# Pi3ToRFIDSchematic.net
KiCad netlist of a schematic drawn in EAGLE
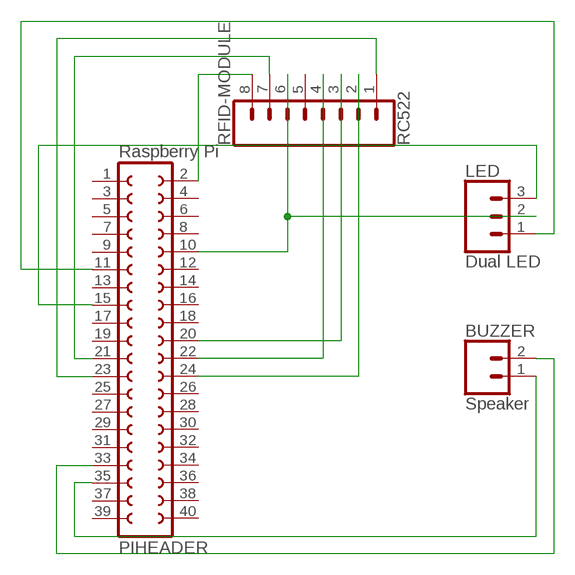
[diagram p0: schematic, sheet 1]
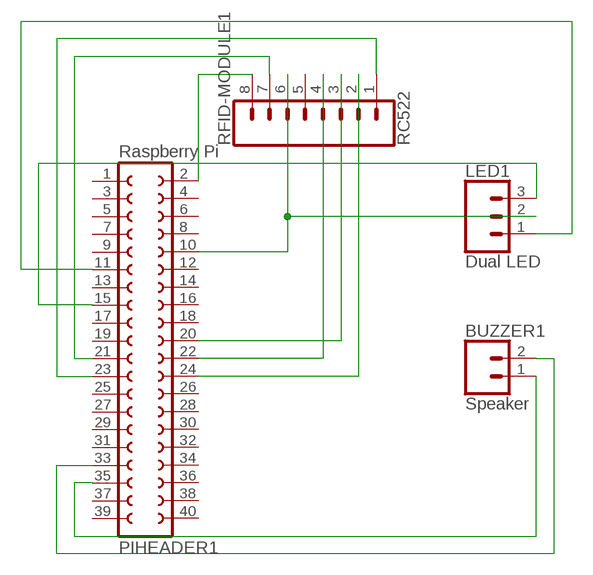
[diagram p1: schematic, sheet 2]

(export (version "E")
  (design (tool "Eeschema 10.0.6"))
  (components
    (comp (ref "BUZZER1")
      (value "Speaker")
      (footprint "eagle-import:MOLEX-1X2")
      (libsource (lib "eagle-import") (part "CONN_02POLAR"))
    )
    (comp (ref "LED1")
      (value "Dual LED")
      (footprint "eagle-import:MOLEX-1X3")
      (libsource (lib "eagle-import") (part "CONN_03POLAR"))
    )
    (comp (ref "PIHEADER1")
      (value "Raspberry Pi")
      (footprint "eagle-import:FE20-2W")
      (libsource (lib "eagle-import") (part "FE20-2W"))
    )
    (comp (ref "RFID-MODULE1")
      (value "RC522")
      (footprint "eagle-import:1X08_LONGPADS")
      (libsource (lib "eagle-import") (part "CONN_08LONGPADS"))
    )
    (comp (ref "BUZZER")
      (value "Speaker")
      (footprint "eagle-import:MOLEX-1X2")
      (libsource (lib "eagle-import") (part "CONN_02POLAR"))
    )
    (comp (ref "LED")
      (value "Dual LED")
      (footprint "eagle-import:MOLEX-1X3")
      (libsource (lib "eagle-import") (part "CONN_03POLAR"))
    )
    (comp (ref "PIHEADER")
      (value "Raspberry Pi")
      (footprint "eagle-import:FE20-2W")
      (libsource (lib "eagle-import") (part "FE20-2W"))
    )
    (comp (ref "RFID-MODULE")
      (value "RC522")
      (footprint "eagle-import:1X08_LONGPADS")
      (libsource (lib "eagle-import") (part "CONN_08LONGPADS"))
    )
  )
  (nets
    (net (code "1") (name "Net-(BUZZER-Pad1)") (class "Default")
      (node (ref "BUZZER") (pin "1") (pinfunction "1_1") (pintype "passive"))
      (node (ref "PIHEADER") (pin "35") (pinfunction "35_35") (pintype "passive"))
    )
    (net (code "2") (name "Net-(BUZZER-Pad2)") (class "Default")
      (node (ref "BUZZER") (pin "2") (pinfunction "2_2") (pintype "passive"))
      (node (ref "PIHEADER") (pin "33") (pinfunction "33_33") (pintype "passive"))
    )
    (net (code "3") (name "Net-(BUZZER1-Pad1)") (class "Default")
      (node (ref "BUZZER1") (pin "1") (pinfunction "1_1") (pintype "passive"))
      (node (ref "PIHEADER1") (pin "35") (pinfunction "35_35") (pintype "passive"))
    )
    (net (code "4") (name "Net-(BUZZER1-Pad2)") (class "Default")
      (node (ref "BUZZER1") (pin "2") (pinfunction "2_2") (pintype "passive"))
      (node (ref "PIHEADER1") (pin "33") (pinfunction "33_33") (pintype "passive"))
    )
    (net (code "5") (name "Net-(LED-Pad1)") (class "Default")
      (node (ref "LED") (pin "1") (pinfunction "1_1") (pintype "passive"))
      (node (ref "PIHEADER") (pin "11") (pinfunction "11_11") (pintype "passive"))
    )
    (net (code "6") (name "Net-(LED-Pad2)") (class "Default")
      (node (ref "LED") (pin "2") (pinfunction "2_2") (pintype "passive"))
      (node (ref "PIHEADER") (pin "10") (pinfunction "10_10") (pintype "passive"))
      (node (ref "RFID-MODULE") (pin "6") (pinfunction "6_6") (pintype "passive"))
    )
    (net (code "7") (name "Net-(LED-Pad3)") (class "Default")
      (node (ref "LED") (pin "3") (pinfunction "3_3") (pintype "passive"))
      (node (ref "PIHEADER") (pin "15") (pinfunction "15_15") (pintype "passive"))
    )
    (net (code "8") (name "Net-(LED1-Pad1)") (class "Default")
      (node (ref "LED1") (pin "1") (pinfunction "1_1") (pintype "passive"))
      (node (ref "PIHEADER1") (pin "11") (pinfunction "11_11") (pintype "passive"))
    )
    (net (code "9") (name "Net-(LED1-Pad2)") (class "Default")
      (node (ref "LED1") (pin "2") (pinfunction "2_2") (pintype "passive"))
      (node (ref "PIHEADER1") (pin "10") (pinfunction "10_10") (pintype "passive"))
      (node (ref "RFID-MODULE1") (pin "6") (pinfunction "6_6") (pintype "passive"))
    )
    (net (code "10") (name "Net-(LED1-Pad3)") (class "Default")
      (node (ref "LED1") (pin "3") (pinfunction "3_3") (pintype "passive"))
      (node (ref "PIHEADER1") (pin "15") (pinfunction "15_15") (pintype "passive"))
    )
    (net (code "11") (name "Net-(PIHEADER-Pad2)") (class "Default")
      (node (ref "PIHEADER") (pin "2") (pinfunction "2_2") (pintype "passive"))
      (node (ref "RFID-MODULE") (pin "8") (pinfunction "8_8") (pintype "passive"))
    )
    (net (code "12") (name "Net-(PIHEADER-Pad20)") (class "Default")
      (node (ref "PIHEADER") (pin "20") (pinfunction "20_20") (pintype "passive"))
      (node (ref "RFID-MODULE") (pin "3") (pinfunction "3_3") (pintype "passive"))
    )
    (net (code "13") (name "Net-(PIHEADER-Pad21)") (class "Default")
      (node (ref "PIHEADER") (pin "21") (pinfunction "21_21") (pintype "passive"))
      (node (ref "RFID-MODULE") (pin "7") (pinfunction "7_7") (pintype "passive"))
    )
    (net (code "14") (name "Net-(PIHEADER-Pad22)") (class "Default")
      (node (ref "PIHEADER") (pin "22") (pinfunction "22_22") (pintype "passive"))
      (node (ref "RFID-MODULE") (pin "4") (pinfunction "4_4") (pintype "passive"))
    )
    (net (code "15") (name "Net-(PIHEADER-Pad23)") (class "Default")
      (node (ref "PIHEADER") (pin "23") (pinfunction "23_23") (pintype "passive"))
      (node (ref "RFID-MODULE") (pin "1") (pinfunction "1_1") (pintype "passive"))
    )
    (net (code "16") (name "Net-(PIHEADER-Pad24)") (class "Default")
      (node (ref "PIHEADER") (pin "24") (pinfunction "24_24") (pintype "passive"))
      (node (ref "RFID-MODULE") (pin "2") (pinfunction "2_2") (pintype "passive"))
    )
    (net (code "17") (name "Net-(PIHEADER1-Pad2)") (class "Default")
      (node (ref "PIHEADER1") (pin "2") (pinfunction "2_2") (pintype "passive"))
      (node (ref "RFID-MODULE1") (pin "8") (pinfunction "8_8") (pintype "passive"))
    )
    (net (code "18") (name "Net-(PIHEADER1-Pad20)") (class "Default")
      (node (ref "PIHEADER1") (pin "20") (pinfunction "20_20") (pintype "passive"))
      (node (ref "RFID-MODULE1") (pin "3") (pinfunction "3_3") (pintype "passive"))
    )
    (net (code "19") (name "Net-(PIHEADER1-Pad21)") (class "Default")
      (node (ref "PIHEADER1") (pin "21") (pinfunction "21_21") (pintype "passive"))
      (node (ref "RFID-MODULE1") (pin "7") (pinfunction "7_7") (pintype "passive"))
    )
    (net (code "20") (name "Net-(PIHEADER1-Pad22)") (class "Default")
      (node (ref "PIHEADER1") (pin "22") (pinfunction "22_22") (pintype "passive"))
      (node (ref "RFID-MODULE1") (pin "4") (pinfunction "4_4") (pintype "passive"))
    )
    (net (code "21") (name "Net-(PIHEADER1-Pad23)") (class "Default")
      (node (ref "PIHEADER1") (pin "23") (pinfunction "23_23") (pintype "passive"))
      (node (ref "RFID-MODULE1") (pin "1") (pinfunction "1_1") (pintype "passive"))
    )
    (net (code "22") (name "Net-(PIHEADER1-Pad24)") (class "Default")
      (node (ref "PIHEADER1") (pin "24") (pinfunction "24_24") (pintype "passive"))
      (node (ref "RFID-MODULE1") (pin "2") (pinfunction "2_2") (pintype "passive"))
    )
    (net (code "23") (name "unconnected-(PIHEADER-Pad1)") (class "Default")
      (node (ref "PIHEADER") (pin "1") (pinfunction "1_1") (pintype "passive"))
    )
    (net (code "24") (name "unconnected-(PIHEADER-Pad3)") (class "Default")
      (node (ref "PIHEADER") (pin "3") (pinfunction "3_3") (pintype "passive"))
    )
    (net (code "25") (name "unconnected-(PIHEADER-Pad4)") (class "Default")
      (node (ref "PIHEADER") (pin "4") (pinfunction "4_4") (pintype "passive"))
    )
    (net (code "26") (name "unconnected-(PIHEADER-Pad5)") (class "Default")
      (node (ref "PIHEADER") (pin "5") (pinfunction "5_5") (pintype "passive"))
    )
    (net (code "27") (name "unconnected-(PIHEADER-Pad6)") (class "Default")
      (node (ref "PIHEADER") (pin "6") (pinfunction "6_6") (pintype "passive"))
    )
    (net (code "28") (name "unconnected-(PIHEADER-Pad7)") (class "Default")
      (node (ref "PIHEADER") (pin "7") (pinfunction "7_7") (pintype "passive"))
    )
    (net (code "29") (name "unconnected-(PIHEADER-Pad8)") (class "Default")
      (node (ref "PIHEADER") (pin "8") (pinfunction "8_8") (pintype "passive"))
    )
    (net (code "30") (name "unconnected-(PIHEADER-Pad9)") (class "Default")
      (node (ref "PIHEADER") (pin "9") (pinfunction "9_9") (pintype "passive"))
    )
    (net (code "31") (name "unconnected-(PIHEADER-Pad12)") (class "Default")
      (node (ref "PIHEADER") (pin "12") (pinfunction "12_12") (pintype "passive"))
    )
    (net (code "32") (name "unconnected-(PIHEADER-Pad13)") (class "Default")
      (node (ref "PIHEADER") (pin "13") (pinfunction "13_13") (pintype "passive"))
    )
    (net (code "33") (name "unconnected-(PIHEADER-Pad14)") (class "Default")
      (node (ref "PIHEADER") (pin "14") (pinfunction "14_14") (pintype "passive"))
    )
    (net (code "34") (name "unconnected-(PIHEADER-Pad16)") (class "Default")
      (node (ref "PIHEADER") (pin "16") (pinfunction "16_16") (pintype "passive"))
    )
    (net (code "35") (name "unconnected-(PIHEADER-Pad17)") (class "Default")
      (node (ref "PIHEADER") (pin "17") (pinfunction "17_17") (pintype "passive"))
    )
    (net (code "36") (name "unconnected-(PIHEADER-Pad18)") (class "Default")
      (node (ref "PIHEADER") (pin "18") (pinfunction "18_18") (pintype "passive"))
    )
    (net (code "37") (name "unconnected-(PIHEADER-Pad19)") (class "Default")
      (node (ref "PIHEADER") (pin "19") (pinfunction "19_19") (pintype "passive"))
    )
    (net (code "38") (name "unconnected-(PIHEADER-Pad25)") (class "Default")
      (node (ref "PIHEADER") (pin "25") (pinfunction "25_25") (pintype "passive"))
    )
    (net (code "39") (name "unconnected-(PIHEADER-Pad26)") (class "Default")
      (node (ref "PIHEADER") (pin "26") (pinfunction "26_26") (pintype "passive"))
    )
    (net (code "40") (name "unconnected-(PIHEADER-Pad27)") (class "Default")
      (node (ref "PIHEADER") (pin "27") (pinfunction "27_27") (pintype "passive"))
    )
    (net (code "41") (name "unconnected-(PIHEADER-Pad28)") (class "Default")
      (node (ref "PIHEADER") (pin "28") (pinfunction "28_28") (pintype "passive"))
    )
    (net (code "42") (name "unconnected-(PIHEADER-Pad29)") (class "Default")
      (node (ref "PIHEADER") (pin "29") (pinfunction "29_29") (pintype "passive"))
    )
    (net (code "43") (name "unconnected-(PIHEADER-Pad30)") (class "Default")
      (node (ref "PIHEADER") (pin "30") (pinfunction "30_30") (pintype "passive"))
    )
    (net (code "44") (name "unconnected-(PIHEADER-Pad31)") (class "Default")
      (node (ref "PIHEADER") (pin "31") (pinfunction "31_31") (pintype "passive"))
    )
    (net (code "45") (name "unconnected-(PIHEADER-Pad32)") (class "Default")
      (node (ref "PIHEADER") (pin "32") (pinfunction "32_32") (pintype "passive"))
    )
    (net (code "46") (name "unconnected-(PIHEADER-Pad34)") (class "Default")
      (node (ref "PIHEADER") (pin "34") (pinfunction "34_34") (pintype "passive"))
    )
    (net (code "47") (name "unconnected-(PIHEADER-Pad36)") (class "Default")
      (node (ref "PIHEADER") (pin "36") (pinfunction "36_36") (pintype "passive"))
    )
    (net (code "48") (name "unconnected-(PIHEADER-Pad37)") (class "Default")
      (node (ref "PIHEADER") (pin "37") (pinfunction "37_37") (pintype "passive"))
    )
    (net (code "49") (name "unconnected-(PIHEADER-Pad38)") (class "Default")
      (node (ref "PIHEADER") (pin "38") (pinfunction "38_38") (pintype "passive"))
    )
    (net (code "50") (name "unconnected-(PIHEADER-Pad39)") (class "Default")
      (node (ref "PIHEADER") (pin "39") (pinfunction "39_39") (pintype "passive"))
    )
    (net (code "51") (name "unconnected-(PIHEADER-Pad40)") (class "Default")
      (node (ref "PIHEADER") (pin "40") (pinfunction "40_40") (pintype "passive"))
    )
    (net (code "52") (name "unconnected-(PIHEADER1-Pad1)") (class "Default")
      (node (ref "PIHEADER1") (pin "1") (pinfunction "1_1") (pintype "passive"))
    )
    (net (code "53") (name "unconnected-(PIHEADER1-Pad3)") (class "Default")
      (node (ref "PIHEADER1") (pin "3") (pinfunction "3_3") (pintype "passive"))
    )
    (net (code "54") (name "unconnected-(PIHEADER1-Pad4)") (class "Default")
      (node (ref "PIHEADER1") (pin "4") (pinfunction "4_4") (pintype "passive"))
    )
    (net (code "55") (name "unconnected-(PIHEADER1-Pad5)") (class "Default")
      (node (ref "PIHEADER1") (pin "5") (pinfunction "5_5") (pintype "passive"))
    )
    (net (code "56") (name "unconnected-(PIHEADER1-Pad6)") (class "Default")
      (node (ref "PIHEADER1") (pin "6") (pinfunction "6_6") (pintype "passive"))
    )
    (net (code "57") (name "unconnected-(PIHEADER1-Pad7)") (class "Default")
      (node (ref "PIHEADER1") (pin "7") (pinfunction "7_7") (pintype "passive"))
    )
    (net (code "58") (name "unconnected-(PIHEADER1-Pad8)") (class "Default")
      (node (ref "PIHEADER1") (pin "8") (pinfunction "8_8") (pintype "passive"))
    )
    (net (code "59") (name "unconnected-(PIHEADER1-Pad9)") (class "Default")
      (node (ref "PIHEADER1") (pin "9") (pinfunction "9_9") (pintype "passive"))
    )
    (net (code "60") (name "unconnected-(PIHEADER1-Pad12)") (class "Default")
      (node (ref "PIHEADER1") (pin "12") (pinfunction "12_12") (pintype "passive"))
    )
    (net (code "61") (name "unconnected-(PIHEADER1-Pad13)") (class "Default")
      (node (ref "PIHEADER1") (pin "13") (pinfunction "13_13") (pintype "passive"))
    )
    (net (code "62") (name "unconnected-(PIHEADER1-Pad14)") (class "Default")
      (node (ref "PIHEADER1") (pin "14") (pinfunction "14_14") (pintype "passive"))
    )
    (net (code "63") (name "unconnected-(PIHEADER1-Pad16)") (class "Default")
      (node (ref "PIHEADER1") (pin "16") (pinfunction "16_16") (pintype "passive"))
    )
    (net (code "64") (name "unconnected-(PIHEADER1-Pad17)") (class "Default")
      (node (ref "PIHEADER1") (pin "17") (pinfunction "17_17") (pintype "passive"))
    )
    (net (code "65") (name "unconnected-(PIHEADER1-Pad18)") (class "Default")
      (node (ref "PIHEADER1") (pin "18") (pinfunction "18_18") (pintype "passive"))
    )
    (net (code "66") (name "unconnected-(PIHEADER1-Pad19)") (class "Default")
      (node (ref "PIHEADER1") (pin "19") (pinfunction "19_19") (pintype "passive"))
    )
    (net (code "67") (name "unconnected-(PIHEADER1-Pad25)") (class "Default")
      (node (ref "PIHEADER1") (pin "25") (pinfunction "25_25") (pintype "passive"))
    )
    (net (code "68") (name "unconnected-(PIHEADER1-Pad26)") (class "Default")
      (node (ref "PIHEADER1") (pin "26") (pinfunction "26_26") (pintype "passive"))
    )
    (net (code "69") (name "unconnected-(PIHEADER1-Pad27)") (class "Default")
      (node (ref "PIHEADER1") (pin "27") (pinfunction "27_27") (pintype "passive"))
    )
    (net (code "70") (name "unconnected-(PIHEADER1-Pad28)") (class "Default")
      (node (ref "PIHEADER1") (pin "28") (pinfunction "28_28") (pintype "passive"))
    )
    (net (code "71") (name "unconnected-(PIHEADER1-Pad29)") (class "Default")
      (node (ref "PIHEADER1") (pin "29") (pinfunction "29_29") (pintype "passive"))
    )
    (net (code "72") (name "unconnected-(PIHEADER1-Pad30)") (class "Default")
      (node (ref "PIHEADER1") (pin "30") (pinfunction "30_30") (pintype "passive"))
    )
    (net (code "73") (name "unconnected-(PIHEADER1-Pad31)") (class "Default")
      (node (ref "PIHEADER1") (pin "31") (pinfunction "31_31") (pintype "passive"))
    )
    (net (code "74") (name "unconnected-(PIHEADER1-Pad32)") (class "Default")
      (node (ref "PIHEADER1") (pin "32") (pinfunction "32_32") (pintype "passive"))
    )
    (net (code "75") (name "unconnected-(PIHEADER1-Pad34)") (class "Default")
      (node (ref "PIHEADER1") (pin "34") (pinfunction "34_34") (pintype "passive"))
    )
    (net (code "76") (name "unconnected-(PIHEADER1-Pad36)") (class "Default")
      (node (ref "PIHEADER1") (pin "36") (pinfunction "36_36") (pintype "passive"))
    )
    (net (code "77") (name "unconnected-(PIHEADER1-Pad37)") (class "Default")
      (node (ref "PIHEADER1") (pin "37") (pinfunction "37_37") (pintype "passive"))
    )
    (net (code "78") (name "unconnected-(PIHEADER1-Pad38)") (class "Default")
      (node (ref "PIHEADER1") (pin "38") (pinfunction "38_38") (pintype "passive"))
    )
    (net (code "79") (name "unconnected-(PIHEADER1-Pad39)") (class "Default")
      (node (ref "PIHEADER1") (pin "39") (pinfunction "39_39") (pintype "passive"))
    )
    (net (code "80") (name "unconnected-(PIHEADER1-Pad40)") (class "Default")
      (node (ref "PIHEADER1") (pin "40") (pinfunction "40_40") (pintype "passive"))
    )
    (net (code "81") (name "unconnected-(RFID-MODULE-Pad5)") (class "Default")
      (node (ref "RFID-MODULE") (pin "5") (pinfunction "5_5") (pintype "passive"))
    )
    (net (code "82") (name "unconnected-(RFID-MODULE1-Pad5)") (class "Default")
      (node (ref "RFID-MODULE1") (pin "5") (pinfunction "5_5") (pintype "passive"))
    )
  )
)
